# digital_clock_run4_copy.net
KiCad netlist of a schematic drawn in EasyEDA
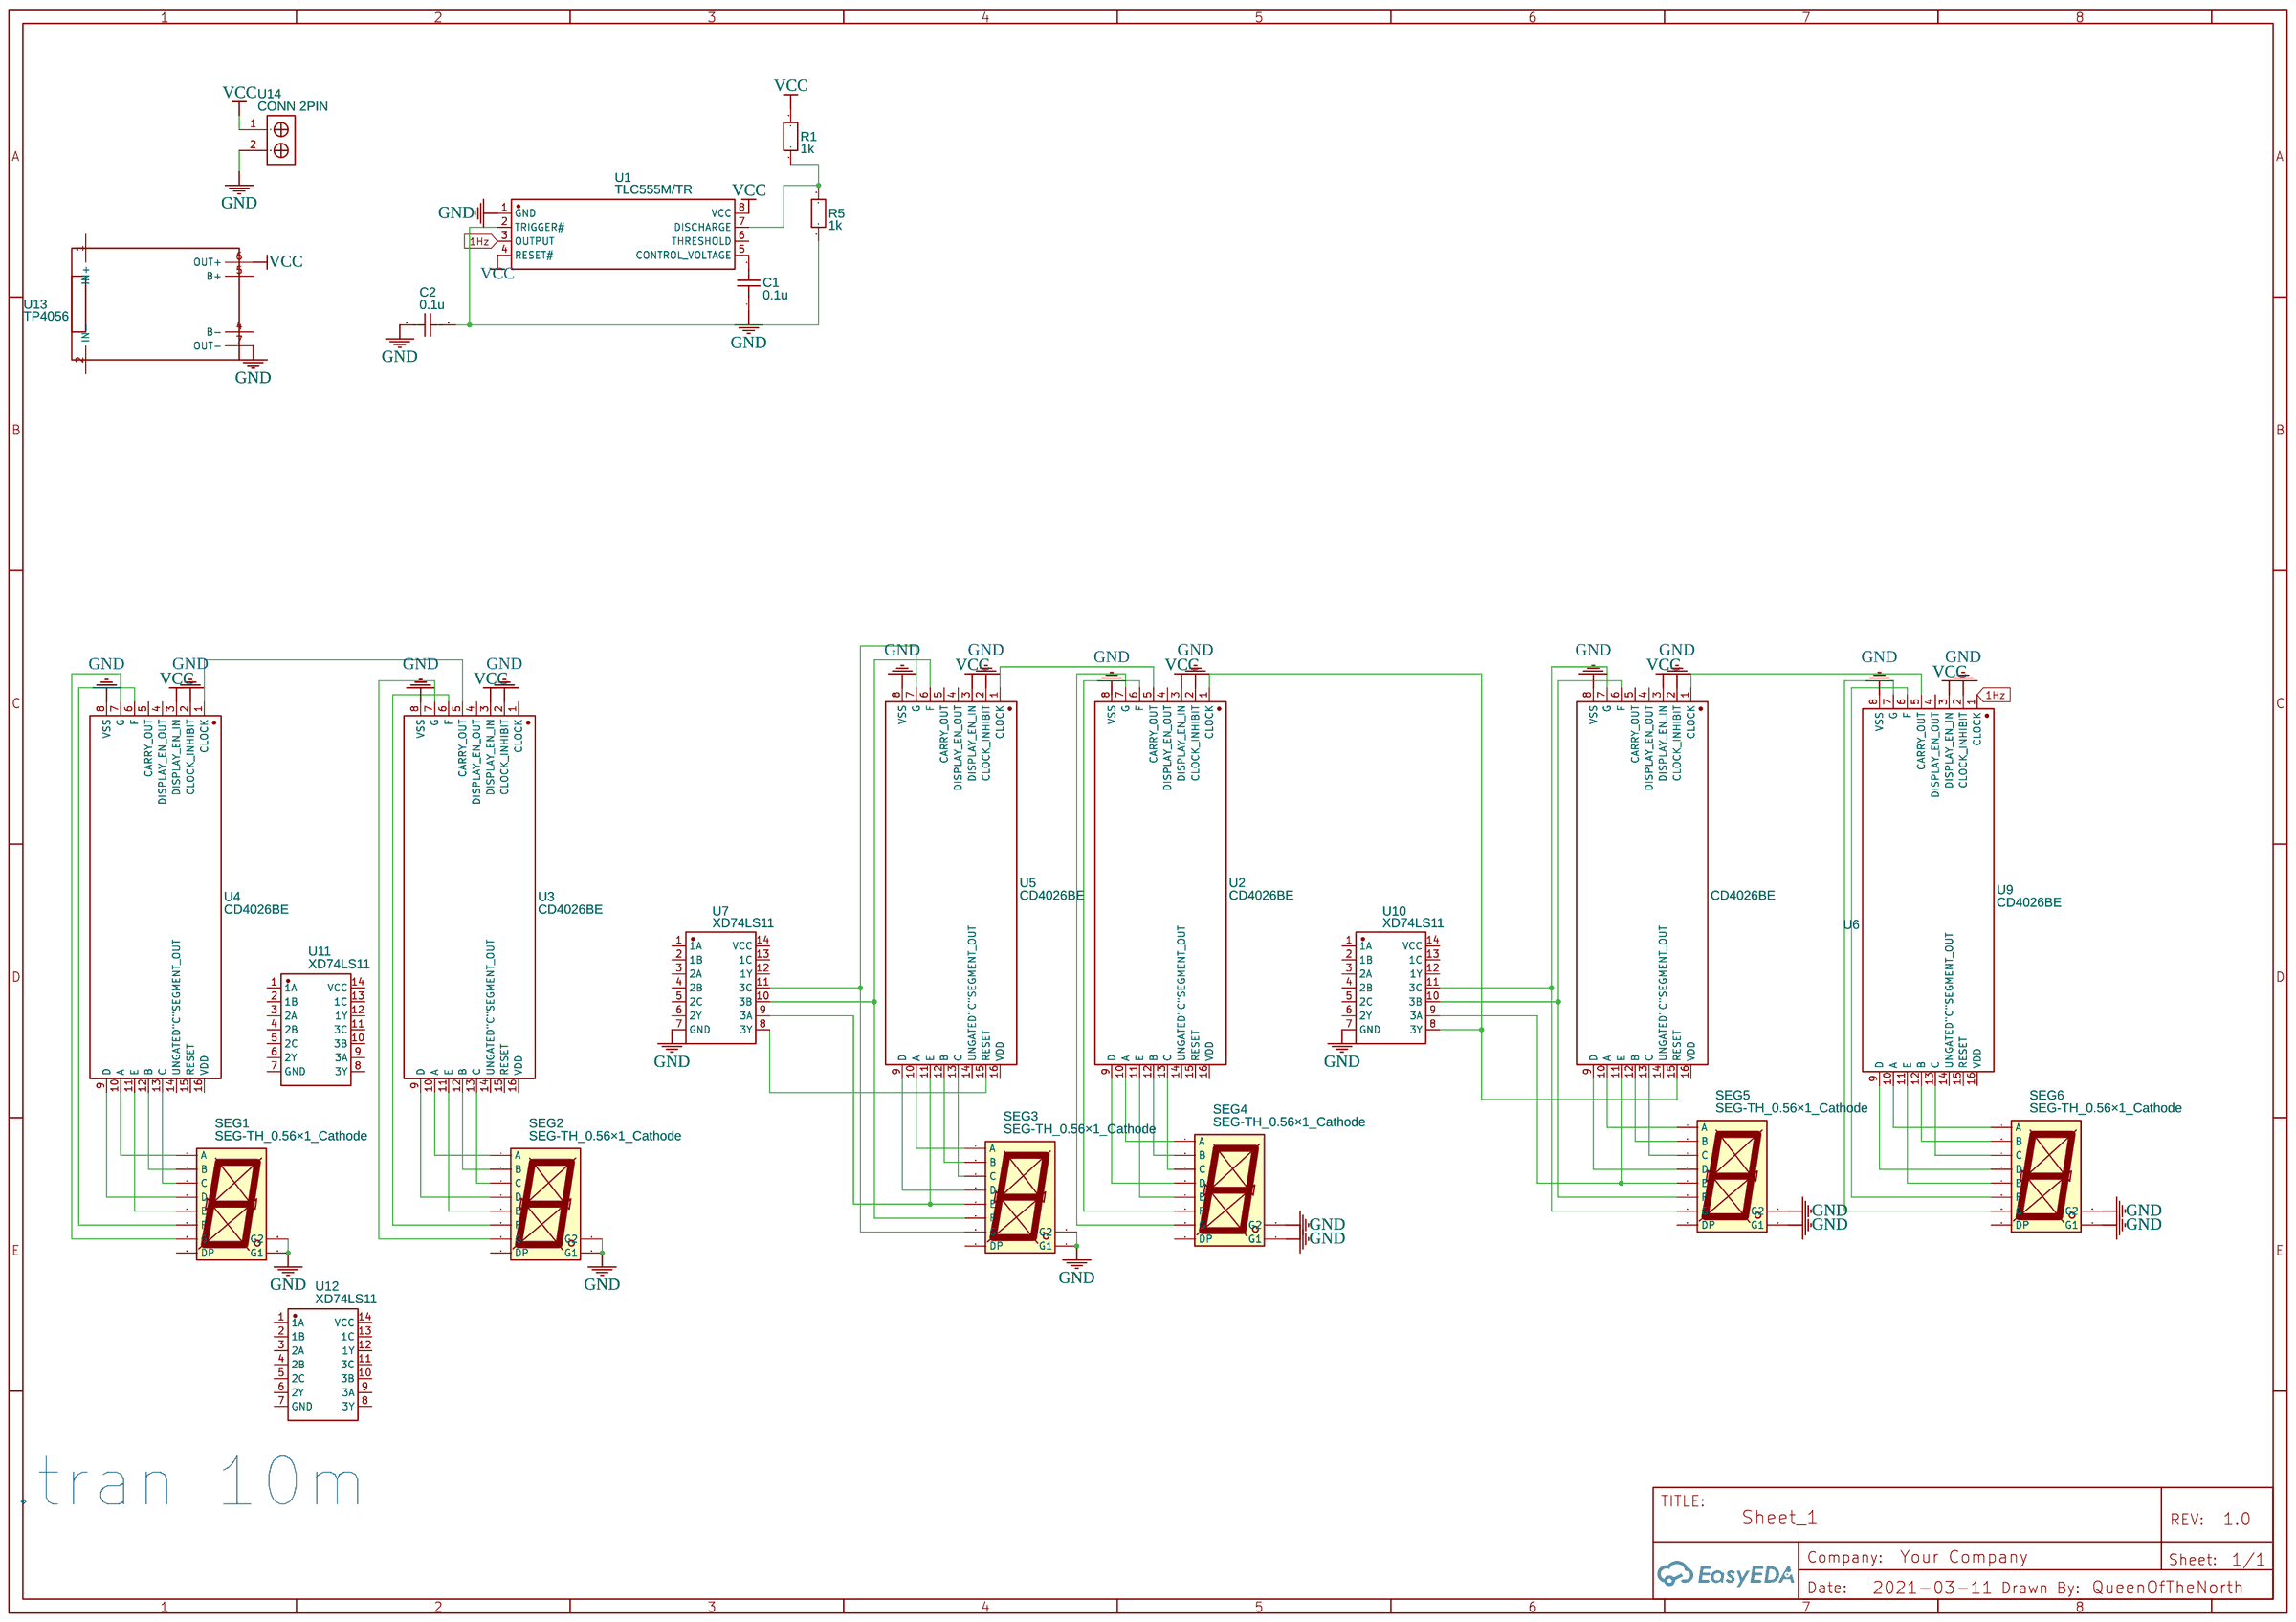
[diagram p0: schematic sheet]

(export (version "E")
  (design (tool "Eeschema 10.0.6"))
  (components
    (comp (ref "C1") (value "0.1u") (libsource (lib "") (part "C_0603_US_1")))
    (comp (ref "C2") (value "0.1u") (libsource (lib "") (part "C_0603_US")))
    (comp (ref "R1") (value "1k") (libsource (lib "") (part "R_0603_EU")))
    (comp (ref "R5") (value "1k") (libsource (lib "") (part "R_0603_EU")))
    (comp (ref "SEG1")
      (value "SEG-TH_0.56×1_Cathode")
      (fields (field (name "BOM_Supplier Part") "C8093"))
      (libsource (lib "") (part "SEG-TH_0.56×1_Cathode"))
    )
    (comp (ref "SEG2")
      (value "SEG-TH_0.56×1_Cathode")
      (fields (field (name "BOM_Supplier Part") "C8093"))
      (libsource (lib "") (part "SEG-TH_0.56×1_Cathode"))
    )
    (comp (ref "SEG3")
      (value "SEG-TH_0.56×1_Cathode")
      (fields (field (name "BOM_Supplier Part") "C8093"))
      (libsource (lib "") (part "SEG-TH_0.56×1_Cathode"))
    )
    (comp (ref "SEG4")
      (value "SEG-TH_0.56×1_Cathode")
      (fields (field (name "BOM_Supplier Part") "C8093"))
      (libsource (lib "") (part "SEG-TH_0.56×1_Cathode"))
    )
    (comp (ref "SEG5")
      (value "SEG-TH_0.56×1_Cathode")
      (fields (field (name "BOM_Supplier Part") "C8093"))
      (libsource (lib "") (part "SEG-TH_0.56×1_Cathode"))
    )
    (comp (ref "SEG6")
      (value "SEG-TH_0.56×1_Cathode")
      (fields (field (name "BOM_Supplier Part") "C8093"))
      (libsource (lib "") (part "SEG-TH_0.56×1_Cathode"))
    )
    (comp (ref "U1")
      (value "TLC555M/TR")
      (fields (field (name "BOM_Supplier Part") "C383061"))
      (libsource (lib "") (part "TLC555M/TR"))
    )
    (comp (ref "U2")
      (value "CD4026BE")
      (fields (field (name "BOM_Supplier Part") "C89909"))
      (libsource (lib "") (part "CD4026BE"))
    )
    (comp (ref "U3")
      (value "CD4026BE")
      (fields (field (name "BOM_Supplier Part") "C89909"))
      (libsource (lib "") (part "CD4026BE"))
    )
    (comp (ref "U4")
      (value "CD4026BE")
      (fields (field (name "BOM_Supplier Part") "C89909"))
      (libsource (lib "") (part "CD4026BE"))
    )
    (comp (ref "U5")
      (value "CD4026BE")
      (fields (field (name "BOM_Supplier Part") "C89909"))
      (libsource (lib "") (part "CD4026BE"))
    )
    (comp (ref "U6")
      (value "CD4026BE")
      (fields (field (name "BOM_Supplier Part") "C89909"))
      (libsource (lib "") (part "CD4026BE"))
    )
    (comp (ref "U7")
      (value "XD74LS11")
      (fields (field (name "BOM_Supplier Part") "C521167"))
      (libsource (lib "") (part "XD74LS11"))
    )
    (comp (ref "U9")
      (value "CD4026BE")
      (fields (field (name "BOM_Supplier Part") "C89909"))
      (libsource (lib "") (part "CD4026BE"))
    )
    (comp (ref "U10")
      (value "XD74LS11")
      (fields (field (name "BOM_Supplier Part") "C521167"))
      (libsource (lib "") (part "XD74LS11"))
    )
    (comp (ref "U11")
      (value "XD74LS11")
      (fields (field (name "BOM_Supplier Part") "C521167"))
      (libsource (lib "") (part "XD74LS11"))
    )
    (comp (ref "U12")
      (value "XD74LS11")
      (fields (field (name "BOM_Supplier Part") "C521167"))
      (libsource (lib "") (part "XD74LS11"))
    )
    (comp (ref "U13")
      (value "TP4056")
      (fields (field (name "BOM_Manufacturer Part") "TP4056-protect"))
      (libsource (lib "") (part "TP4056"))
    )
    (comp (ref "U14")
      (value "CONN 2PIN")
      (fields
        (field (name "BOM_Manufacturer Part") "Terminal Block")
        (field (name "BOM_Supplier Part") "undefined")
      )
      (libsource (lib "") (part "CONN 2PIN"))
    )
  )
  (nets
    (net (code "1") (name "1Hz") (class "Default")
      (node (ref "U1") (pin "3") (pinfunction "OUTPUT_3") (pintype "unspecified"))
      (node (ref "U9") (pin "1") (pinfunction "CLOCK_1") (pintype "unspecified"))
    )
    (net (code "2") (name "GND") (class "Default")
      (node (ref "C1") (pin "1") (pinfunction "1_1") (pintype "unspecified"))
      (node (ref "C2") (pin "1") (pinfunction "1_1") (pintype "unspecified"))
      (node (ref "SEG1") (pin "3") (pinfunction "G1_3") (pintype "unspecified"))
      (node (ref "SEG1") (pin "8") (pinfunction "G2_8") (pintype "unspecified"))
      (node (ref "SEG2") (pin "3") (pinfunction "G1_3") (pintype "unspecified"))
      (node (ref "SEG2") (pin "8") (pinfunction "G2_8") (pintype "unspecified"))
      (node (ref "SEG3") (pin "3") (pinfunction "G1_3") (pintype "unspecified"))
      (node (ref "SEG3") (pin "8") (pinfunction "G2_8") (pintype "unspecified"))
      (node (ref "SEG4") (pin "3") (pinfunction "G1_3") (pintype "unspecified"))
      (node (ref "SEG4") (pin "8") (pinfunction "G2_8") (pintype "unspecified"))
      (node (ref "SEG5") (pin "3") (pinfunction "G1_3") (pintype "unspecified"))
      (node (ref "SEG5") (pin "8") (pinfunction "G2_8") (pintype "unspecified"))
      (node (ref "SEG6") (pin "3") (pinfunction "G1_3") (pintype "unspecified"))
      (node (ref "SEG6") (pin "8") (pinfunction "G2_8") (pintype "unspecified"))
      (node (ref "U1") (pin "1") (pinfunction "GND_1") (pintype "unspecified"))
      (node (ref "U10") (pin "7") (pinfunction "GND_7") (pintype "unspecified"))
      (node (ref "U13") (pin "7") (pinfunction "OUT-_7") (pintype "unspecified"))
      (node (ref "U14") (pin "2") (pinfunction "2_2") (pintype "unspecified"))
      (node (ref "U2") (pin "2") (pinfunction "CLOCK_INHIBIT_2") (pintype "unspecified"))
      (node (ref "U3") (pin "2") (pinfunction "CLOCK_INHIBIT_2") (pintype "unspecified"))
      (node (ref "U3") (pin "8") (pinfunction "VSS_8") (pintype "unspecified"))
      (node (ref "U4") (pin "2") (pinfunction "CLOCK_INHIBIT_2") (pintype "unspecified"))
      (node (ref "U4") (pin "8") (pinfunction "VSS_8") (pintype "unspecified"))
      (node (ref "U5") (pin "2") (pinfunction "CLOCK_INHIBIT_2") (pintype "unspecified"))
      (node (ref "U5") (pin "8") (pinfunction "VSS_8") (pintype "unspecified"))
      (node (ref "U6") (pin "2") (pinfunction "CLOCK_INHIBIT_2") (pintype "unspecified"))
      (node (ref "U6") (pin "8") (pinfunction "VSS_8") (pintype "unspecified"))
      (node (ref "U7") (pin "7") (pinfunction "GND_7") (pintype "unspecified"))
      (node (ref "U9") (pin "2") (pinfunction "CLOCK_INHIBIT_2") (pintype "unspecified"))
      (node (ref "U9") (pin "8") (pinfunction "VSS_8") (pintype "unspecified"))
    )
    (net (code "3") (name "Net-(SEG1-A)") (class "Default")
      (node (ref "SEG1") (pin "7") (pinfunction "A_7") (pintype "unspecified"))
      (node (ref "U4") (pin "10") (pinfunction "A_10") (pintype "unspecified"))
    )
    (net (code "4") (name "Net-(SEG1-B)") (class "Default")
      (node (ref "SEG1") (pin "6") (pinfunction "B_6") (pintype "unspecified"))
      (node (ref "U4") (pin "12") (pinfunction "B_12") (pintype "unspecified"))
    )
    (net (code "5") (name "Net-(SEG1-C)") (class "Default")
      (node (ref "SEG1") (pin "4") (pinfunction "C_4") (pintype "unspecified"))
      (node (ref "U4") (pin "13") (pinfunction "C_13") (pintype "unspecified"))
    )
    (net (code "6") (name "Net-(SEG1-D)") (class "Default")
      (node (ref "SEG1") (pin "2") (pinfunction "D_2") (pintype "unspecified"))
      (node (ref "U4") (pin "9") (pinfunction "D_9") (pintype "unspecified"))
    )
    (net (code "7") (name "Net-(SEG1-E)") (class "Default")
      (node (ref "SEG1") (pin "1") (pinfunction "E_1") (pintype "unspecified"))
      (node (ref "U4") (pin "11") (pinfunction "E_11") (pintype "unspecified"))
    )
    (net (code "8") (name "Net-(SEG1-F)") (class "Default")
      (node (ref "SEG1") (pin "9") (pinfunction "F_9") (pintype "unspecified"))
      (node (ref "U4") (pin "6") (pinfunction "F_6") (pintype "unspecified"))
    )
    (net (code "9") (name "Net-(SEG1-G)") (class "Default")
      (node (ref "SEG1") (pin "10") (pinfunction "G_10") (pintype "unspecified"))
      (node (ref "U4") (pin "7") (pinfunction "G_7") (pintype "unspecified"))
    )
    (net (code "10") (name "Net-(SEG2-A)") (class "Default")
      (node (ref "SEG2") (pin "7") (pinfunction "A_7") (pintype "unspecified"))
      (node (ref "U3") (pin "10") (pinfunction "A_10") (pintype "unspecified"))
    )
    (net (code "11") (name "Net-(SEG2-B)") (class "Default")
      (node (ref "SEG2") (pin "6") (pinfunction "B_6") (pintype "unspecified"))
      (node (ref "U3") (pin "12") (pinfunction "B_12") (pintype "unspecified"))
    )
    (net (code "12") (name "Net-(SEG2-C)") (class "Default")
      (node (ref "SEG2") (pin "4") (pinfunction "C_4") (pintype "unspecified"))
      (node (ref "U3") (pin "13") (pinfunction "C_13") (pintype "unspecified"))
    )
    (net (code "13") (name "Net-(SEG2-D)") (class "Default")
      (node (ref "SEG2") (pin "2") (pinfunction "D_2") (pintype "unspecified"))
      (node (ref "U3") (pin "9") (pinfunction "D_9") (pintype "unspecified"))
    )
    (net (code "14") (name "Net-(SEG2-E)") (class "Default")
      (node (ref "SEG2") (pin "1") (pinfunction "E_1") (pintype "unspecified"))
      (node (ref "U3") (pin "11") (pinfunction "E_11") (pintype "unspecified"))
    )
    (net (code "15") (name "Net-(SEG2-F)") (class "Default")
      (node (ref "SEG2") (pin "9") (pinfunction "F_9") (pintype "unspecified"))
      (node (ref "U3") (pin "6") (pinfunction "F_6") (pintype "unspecified"))
    )
    (net (code "16") (name "Net-(SEG2-G)") (class "Default")
      (node (ref "SEG2") (pin "10") (pinfunction "G_10") (pintype "unspecified"))
      (node (ref "U3") (pin "7") (pinfunction "G_7") (pintype "unspecified"))
    )
    (net (code "17") (name "Net-(SEG3-A)") (class "Default")
      (node (ref "SEG3") (pin "7") (pinfunction "A_7") (pintype "unspecified"))
      (node (ref "U5") (pin "10") (pinfunction "A_10") (pintype "unspecified"))
    )
    (net (code "18") (name "Net-(SEG3-B)") (class "Default")
      (node (ref "SEG3") (pin "6") (pinfunction "B_6") (pintype "unspecified"))
      (node (ref "U5") (pin "12") (pinfunction "B_12") (pintype "unspecified"))
    )
    (net (code "19") (name "Net-(SEG3-C)") (class "Default")
      (node (ref "SEG3") (pin "4") (pinfunction "C_4") (pintype "unspecified"))
      (node (ref "U5") (pin "13") (pinfunction "C_13") (pintype "unspecified"))
    )
    (net (code "20") (name "Net-(SEG3-D)") (class "Default")
      (node (ref "SEG3") (pin "2") (pinfunction "D_2") (pintype "unspecified"))
      (node (ref "U5") (pin "9") (pinfunction "D_9") (pintype "unspecified"))
    )
    (net (code "21") (name "Net-(SEG3-E)") (class "Default")
      (node (ref "SEG3") (pin "1") (pinfunction "E_1") (pintype "unspecified"))
      (node (ref "U5") (pin "11") (pinfunction "E_11") (pintype "unspecified"))
      (node (ref "U7") (pin "9") (pinfunction "3A_9") (pintype "unspecified"))
    )
    (net (code "22") (name "Net-(SEG3-F)") (class "Default")
      (node (ref "SEG3") (pin "9") (pinfunction "F_9") (pintype "unspecified"))
      (node (ref "U5") (pin "6") (pinfunction "F_6") (pintype "unspecified"))
      (node (ref "U7") (pin "10") (pinfunction "3B_10") (pintype "unspecified"))
    )
    (net (code "23") (name "Net-(SEG3-G)") (class "Default")
      (node (ref "SEG3") (pin "10") (pinfunction "G_10") (pintype "unspecified"))
      (node (ref "U5") (pin "7") (pinfunction "G_7") (pintype "unspecified"))
      (node (ref "U7") (pin "11") (pinfunction "3C_11") (pintype "unspecified"))
    )
    (net (code "24") (name "Net-(SEG4-A)") (class "Default")
      (node (ref "SEG4") (pin "7") (pinfunction "A_7") (pintype "unspecified"))
      (node (ref "U2") (pin "10") (pinfunction "A_10") (pintype "unspecified"))
    )
    (net (code "25") (name "Net-(SEG4-B)") (class "Default")
      (node (ref "SEG4") (pin "6") (pinfunction "B_6") (pintype "unspecified"))
      (node (ref "U2") (pin "12") (pinfunction "B_12") (pintype "unspecified"))
    )
    (net (code "26") (name "Net-(SEG4-C)") (class "Default")
      (node (ref "SEG4") (pin "4") (pinfunction "C_4") (pintype "unspecified"))
      (node (ref "U2") (pin "13") (pinfunction "C_13") (pintype "unspecified"))
    )
    (net (code "27") (name "Net-(SEG4-D)") (class "Default")
      (node (ref "SEG4") (pin "2") (pinfunction "D_2") (pintype "unspecified"))
      (node (ref "U2") (pin "9") (pinfunction "D_9") (pintype "unspecified"))
    )
    (net (code "28") (name "Net-(SEG4-E)") (class "Default")
      (node (ref "SEG4") (pin "1") (pinfunction "E_1") (pintype "unspecified"))
      (node (ref "U2") (pin "11") (pinfunction "E_11") (pintype "unspecified"))
    )
    (net (code "29") (name "Net-(SEG4-F)") (class "Default")
      (node (ref "SEG4") (pin "9") (pinfunction "F_9") (pintype "unspecified"))
      (node (ref "U2") (pin "6") (pinfunction "F_6") (pintype "unspecified"))
    )
    (net (code "30") (name "Net-(SEG4-G)") (class "Default")
      (node (ref "SEG4") (pin "10") (pinfunction "G_10") (pintype "unspecified"))
      (node (ref "U2") (pin "7") (pinfunction "G_7") (pintype "unspecified"))
    )
    (net (code "31") (name "Net-(SEG5-A)") (class "Default")
      (node (ref "SEG5") (pin "7") (pinfunction "A_7") (pintype "unspecified"))
      (node (ref "U6") (pin "10") (pinfunction "A_10") (pintype "unspecified"))
    )
    (net (code "32") (name "Net-(SEG5-B)") (class "Default")
      (node (ref "SEG5") (pin "6") (pinfunction "B_6") (pintype "unspecified"))
      (node (ref "U6") (pin "12") (pinfunction "B_12") (pintype "unspecified"))
    )
    (net (code "33") (name "Net-(SEG5-C)") (class "Default")
      (node (ref "SEG5") (pin "4") (pinfunction "C_4") (pintype "unspecified"))
      (node (ref "U6") (pin "13") (pinfunction "C_13") (pintype "unspecified"))
    )
    (net (code "34") (name "Net-(SEG5-D)") (class "Default")
      (node (ref "SEG5") (pin "2") (pinfunction "D_2") (pintype "unspecified"))
      (node (ref "U6") (pin "9") (pinfunction "D_9") (pintype "unspecified"))
    )
    (net (code "35") (name "Net-(SEG5-E)") (class "Default")
      (node (ref "SEG5") (pin "1") (pinfunction "E_1") (pintype "unspecified"))
      (node (ref "U10") (pin "9") (pinfunction "3A_9") (pintype "unspecified"))
      (node (ref "U6") (pin "11") (pinfunction "E_11") (pintype "unspecified"))
    )
    (net (code "36") (name "Net-(SEG5-F)") (class "Default")
      (node (ref "SEG5") (pin "9") (pinfunction "F_9") (pintype "unspecified"))
      (node (ref "U10") (pin "10") (pinfunction "3B_10") (pintype "unspecified"))
      (node (ref "U6") (pin "6") (pinfunction "F_6") (pintype "unspecified"))
    )
    (net (code "37") (name "Net-(SEG5-G)") (class "Default")
      (node (ref "SEG5") (pin "10") (pinfunction "G_10") (pintype "unspecified"))
      (node (ref "U10") (pin "11") (pinfunction "3C_11") (pintype "unspecified"))
      (node (ref "U6") (pin "7") (pinfunction "G_7") (pintype "unspecified"))
    )
    (net (code "38") (name "Net-(SEG6-A)") (class "Default")
      (node (ref "SEG6") (pin "7") (pinfunction "A_7") (pintype "unspecified"))
      (node (ref "U9") (pin "10") (pinfunction "A_10") (pintype "unspecified"))
    )
    (net (code "39") (name "Net-(SEG6-B)") (class "Default")
      (node (ref "SEG6") (pin "6") (pinfunction "B_6") (pintype "unspecified"))
      (node (ref "U9") (pin "12") (pinfunction "B_12") (pintype "unspecified"))
    )
    (net (code "40") (name "Net-(SEG6-C)") (class "Default")
      (node (ref "SEG6") (pin "4") (pinfunction "C_4") (pintype "unspecified"))
      (node (ref "U9") (pin "13") (pinfunction "C_13") (pintype "unspecified"))
    )
    (net (code "41") (name "Net-(SEG6-D)") (class "Default")
      (node (ref "SEG6") (pin "2") (pinfunction "D_2") (pintype "unspecified"))
      (node (ref "U9") (pin "9") (pinfunction "D_9") (pintype "unspecified"))
    )
    (net (code "42") (name "Net-(SEG6-E)") (class "Default")
      (node (ref "SEG6") (pin "1") (pinfunction "E_1") (pintype "unspecified"))
      (node (ref "U9") (pin "11") (pinfunction "E_11") (pintype "unspecified"))
    )
    (net (code "43") (name "Net-(SEG6-F)") (class "Default")
      (node (ref "SEG6") (pin "9") (pinfunction "F_9") (pintype "unspecified"))
      (node (ref "U9") (pin "6") (pinfunction "F_6") (pintype "unspecified"))
    )
    (net (code "44") (name "Net-(SEG6-G)") (class "Default")
      (node (ref "SEG6") (pin "10") (pinfunction "G_10") (pintype "unspecified"))
      (node (ref "U9") (pin "7") (pinfunction "G_7") (pintype "unspecified"))
    )
    (net (code "45") (name "Net-(U1-CONTROL_VOLTAGE)") (class "Default")
      (node (ref "C1") (pin "2") (pinfunction "2_2") (pintype "unspecified"))
      (node (ref "U1") (pin "5") (pinfunction "CONTROL_VOLTAGE_5") (pintype "unspecified"))
    )
    (net (code "46") (name "Net-(U1-DISCHARGE)") (class "Default")
      (node (ref "R1") (pin "1") (pinfunction "1_1") (pintype "unspecified"))
      (node (ref "R5") (pin "2") (pinfunction "2_2") (pintype "unspecified"))
      (node (ref "U1") (pin "7") (pinfunction "DISCHARGE_7") (pintype "unspecified"))
    )
    (net (code "47") (name "Net-(U1-TRIGGER#)") (class "Default")
      (node (ref "C2") (pin "2") (pinfunction "2_2") (pintype "unspecified"))
      (node (ref "R5") (pin "1") (pinfunction "1_1") (pintype "unspecified"))
      (node (ref "U1") (pin "2") (pinfunction "TRIGGER#_2") (pintype "unspecified"))
    )
    (net (code "48") (name "Net-(U2-CARRY_OUT)") (class "Default")
      (node (ref "U2") (pin "5") (pinfunction "CARRY_OUT_5") (pintype "unspecified"))
      (node (ref "U5") (pin "1") (pinfunction "CLOCK_1") (pintype "unspecified"))
    )
    (net (code "49") (name "Net-(U3-CARRY_OUT)") (class "Default")
      (node (ref "U3") (pin "5") (pinfunction "CARRY_OUT_5") (pintype "unspecified"))
      (node (ref "U4") (pin "1") (pinfunction "CLOCK_1") (pintype "unspecified"))
    )
    (net (code "50") (name "Net-(U5-RESET)") (class "Default")
      (node (ref "U5") (pin "15") (pinfunction "RESET_15") (pintype "unspecified"))
      (node (ref "U7") (pin "8") (pinfunction "3Y_8") (pintype "unspecified"))
    )
    (net (code "51") (name "Net-(U6-CLOCK)") (class "Default")
      (node (ref "U6") (pin "1") (pinfunction "CLOCK_1") (pintype "unspecified"))
      (node (ref "U9") (pin "5") (pinfunction "CARRY_OUT_5") (pintype "unspecified"))
    )
    (net (code "52") (name "Net-(U10-3Y)") (class "Default")
      (node (ref "U10") (pin "8") (pinfunction "3Y_8") (pintype "unspecified"))
      (node (ref "U2") (pin "1") (pinfunction "CLOCK_1") (pintype "unspecified"))
      (node (ref "U6") (pin "15") (pinfunction "RESET_15") (pintype "unspecified"))
    )
    (net (code "53") (name "VCC") (class "Default")
      (node (ref "R1") (pin "2") (pinfunction "2_2") (pintype "unspecified"))
      (node (ref "U1") (pin "4") (pinfunction "RESET#_4") (pintype "unspecified"))
      (node (ref "U1") (pin "8") (pinfunction "VCC_8") (pintype "unspecified"))
      (node (ref "U13") (pin "6") (pinfunction "OUT+_6") (pintype "unspecified"))
      (node (ref "U14") (pin "1") (pinfunction "1_1") (pintype "unspecified"))
      (node (ref "U2") (pin "3") (pinfunction "DISPLAY_EN_IN_3") (pintype "unspecified"))
      (node (ref "U3") (pin "3") (pinfunction "DISPLAY_EN_IN_3") (pintype "unspecified"))
      (node (ref "U4") (pin "3") (pinfunction "DISPLAY_EN_IN_3") (pintype "unspecified"))
      (node (ref "U5") (pin "3") (pinfunction "DISPLAY_EN_IN_3") (pintype "unspecified"))
      (node (ref "U6") (pin "3") (pinfunction "DISPLAY_EN_IN_3") (pintype "unspecified"))
      (node (ref "U9") (pin "3") (pinfunction "DISPLAY_EN_IN_3") (pintype "unspecified"))
    )
    (net (code "54") (name "unconnected-(SEG1-DP-Pad5)") (class "Default")
      (node (ref "SEG1") (pin "5") (pinfunction "DP_5") (pintype "unspecified"))
    )
    (net (code "55") (name "unconnected-(SEG2-DP-Pad5)") (class "Default")
      (node (ref "SEG2") (pin "5") (pinfunction "DP_5") (pintype "unspecified"))
    )
    (net (code "56") (name "unconnected-(SEG3-DP-Pad5)") (class "Default")
      (node (ref "SEG3") (pin "5") (pinfunction "DP_5") (pintype "unspecified"))
    )
    (net (code "57") (name "unconnected-(SEG4-DP-Pad5)") (class "Default")
      (node (ref "SEG4") (pin "5") (pinfunction "DP_5") (pintype "unspecified"))
    )
    (net (code "58") (name "unconnected-(SEG5-DP-Pad5)") (class "Default")
      (node (ref "SEG5") (pin "5") (pinfunction "DP_5") (pintype "unspecified"))
    )
    (net (code "59") (name "unconnected-(SEG6-DP-Pad5)") (class "Default")
      (node (ref "SEG6") (pin "5") (pinfunction "DP_5") (pintype "unspecified"))
    )
    (net (code "60") (name "unconnected-(U1-THRESHOLD-Pad6)") (class "Default")
      (node (ref "U1") (pin "6") (pinfunction "THRESHOLD_6") (pintype "unspecified"))
    )
    (net (code "61") (name "unconnected-(U2-DISPLAY_EN_OUT-Pad4)") (class "Default")
      (node (ref "U2") (pin "4") (pinfunction "DISPLAY_EN_OUT_4") (pintype "unspecified"))
    )
    (net (code "62") (name "unconnected-(U2-RESET-Pad15)") (class "Default")
      (node (ref "U2") (pin "15") (pinfunction "RESET_15") (pintype "unspecified"))
    )
    (net (code "63") (name "unconnected-(U2-UNGATED\"C\"SEGMENT_OUT-Pad14)") (class "Default")
      (node (ref "U2") (pin "14") (pinfunction "UNGATED\"C\"SEGMENT_OUT_14") (pintype "unspecified"))
    )
    (net (code "64") (name "unconnected-(U2-VDD-Pad16)") (class "Default")
      (node (ref "U2") (pin "16") (pinfunction "VDD_16") (pintype "unspecified"))
    )
    (net (code "65") (name "unconnected-(U2-VSS-Pad8)") (class "Default")
      (node (ref "U2") (pin "8") (pinfunction "VSS_8") (pintype "unspecified"))
    )
    (net (code "66") (name "unconnected-(U3-CLOCK-Pad1)") (class "Default")
      (node (ref "U3") (pin "1") (pinfunction "CLOCK_1") (pintype "unspecified"))
    )
    (net (code "67") (name "unconnected-(U3-DISPLAY_EN_OUT-Pad4)") (class "Default")
      (node (ref "U3") (pin "4") (pinfunction "DISPLAY_EN_OUT_4") (pintype "unspecified"))
    )
    (net (code "68") (name "unconnected-(U3-RESET-Pad15)") (class "Default")
      (node (ref "U3") (pin "15") (pinfunction "RESET_15") (pintype "unspecified"))
    )
    (net (code "69") (name "unconnected-(U3-UNGATED\"C\"SEGMENT_OUT-Pad14)") (class "Default")
      (node (ref "U3") (pin "14") (pinfunction "UNGATED\"C\"SEGMENT_OUT_14") (pintype "unspecified"))
    )
    (net (code "70") (name "unconnected-(U3-VDD-Pad16)") (class "Default")
      (node (ref "U3") (pin "16") (pinfunction "VDD_16") (pintype "unspecified"))
    )
    (net (code "71") (name "unconnected-(U4-CARRY_OUT-Pad5)") (class "Default")
      (node (ref "U4") (pin "5") (pinfunction "CARRY_OUT_5") (pintype "unspecified"))
    )
    (net (code "72") (name "unconnected-(U4-DISPLAY_EN_OUT-Pad4)") (class "Default")
      (node (ref "U4") (pin "4") (pinfunction "DISPLAY_EN_OUT_4") (pintype "unspecified"))
    )
    (net (code "73") (name "unconnected-(U4-RESET-Pad15)") (class "Default")
      (node (ref "U4") (pin "15") (pinfunction "RESET_15") (pintype "unspecified"))
    )
    (net (code "74") (name "unconnected-(U4-UNGATED\"C\"SEGMENT_OUT-Pad14)") (class "Default")
      (node (ref "U4") (pin "14") (pinfunction "UNGATED\"C\"SEGMENT_OUT_14") (pintype "unspecified"))
    )
    (net (code "75") (name "unconnected-(U4-VDD-Pad16)") (class "Default")
      (node (ref "U4") (pin "16") (pinfunction "VDD_16") (pintype "unspecified"))
    )
    (net (code "76") (name "unconnected-(U5-CARRY_OUT-Pad5)") (class "Default")
      (node (ref "U5") (pin "5") (pinfunction "CARRY_OUT_5") (pintype "unspecified"))
    )
    (net (code "77") (name "unconnected-(U5-DISPLAY_EN_OUT-Pad4)") (class "Default")
      (node (ref "U5") (pin "4") (pinfunction "DISPLAY_EN_OUT_4") (pintype "unspecified"))
    )
    (net (code "78") (name "unconnected-(U5-UNGATED\"C\"SEGMENT_OUT-Pad14)") (class "Default")
      (node (ref "U5") (pin "14") (pinfunction "UNGATED\"C\"SEGMENT_OUT_14") (pintype "unspecified"))
    )
    (net (code "79") (name "unconnected-(U5-VDD-Pad16)") (class "Default")
      (node (ref "U5") (pin "16") (pinfunction "VDD_16") (pintype "unspecified"))
    )
    (net (code "80") (name "unconnected-(U6-CARRY_OUT-Pad5)") (class "Default")
      (node (ref "U6") (pin "5") (pinfunction "CARRY_OUT_5") (pintype "unspecified"))
    )
    (net (code "81") (name "unconnected-(U6-DISPLAY_EN_OUT-Pad4)") (class "Default")
      (node (ref "U6") (pin "4") (pinfunction "DISPLAY_EN_OUT_4") (pintype "unspecified"))
    )
    (net (code "82") (name "unconnected-(U6-UNGATED\"C\"SEGMENT_OUT-Pad14)") (class "Default")
      (node (ref "U6") (pin "14") (pinfunction "UNGATED\"C\"SEGMENT_OUT_14") (pintype "unspecified"))
    )
    (net (code "83") (name "unconnected-(U6-VDD-Pad16)") (class "Default")
      (node (ref "U6") (pin "16") (pinfunction "VDD_16") (pintype "unspecified"))
    )
    (net (code "84") (name "unconnected-(U7-1A-Pad1)") (class "Default")
      (node (ref "U7") (pin "1") (pinfunction "1A_1") (pintype "unspecified"))
    )
    (net (code "85") (name "unconnected-(U7-1B-Pad2)") (class "Default")
      (node (ref "U7") (pin "2") (pinfunction "1B_2") (pintype "unspecified"))
    )
    (net (code "86") (name "unconnected-(U7-1C-Pad13)") (class "Default")
      (node (ref "U7") (pin "13") (pinfunction "1C_13") (pintype "unspecified"))
    )
    (net (code "87") (name "unconnected-(U7-1Y-Pad12)") (class "Default")
      (node (ref "U7") (pin "12") (pinfunction "1Y_12") (pintype "unspecified"))
    )
    (net (code "88") (name "unconnected-(U7-2A-Pad3)") (class "Default")
      (node (ref "U7") (pin "3") (pinfunction "2A_3") (pintype "unspecified"))
    )
    (net (code "89") (name "unconnected-(U7-2B-Pad4)") (class "Default")
      (node (ref "U7") (pin "4") (pinfunction "2B_4") (pintype "unspecified"))
    )
    (net (code "90") (name "unconnected-(U7-2C-Pad5)") (class "Default")
      (node (ref "U7") (pin "5") (pinfunction "2C_5") (pintype "unspecified"))
    )
    (net (code "91") (name "unconnected-(U7-2Y-Pad6)") (class "Default")
      (node (ref "U7") (pin "6") (pinfunction "2Y_6") (pintype "unspecified"))
    )
    (net (code "92") (name "unconnected-(U7-VCC-Pad14)") (class "Default")
      (node (ref "U7") (pin "14") (pinfunction "VCC_14") (pintype "unspecified"))
    )
    (net (code "93") (name "unconnected-(U9-DISPLAY_EN_OUT-Pad4)") (class "Default")
      (node (ref "U9") (pin "4") (pinfunction "DISPLAY_EN_OUT_4") (pintype "unspecified"))
    )
    (net (code "94") (name "unconnected-(U9-RESET-Pad15)") (class "Default")
      (node (ref "U9") (pin "15") (pinfunction "RESET_15") (pintype "unspecified"))
    )
    (net (code "95") (name "unconnected-(U9-UNGATED\"C\"SEGMENT_OUT-Pad14)") (class "Default")
      (node (ref "U9") (pin "14") (pinfunction "UNGATED\"C\"SEGMENT_OUT_14") (pintype "unspecified"))
    )
    (net (code "96") (name "unconnected-(U9-VDD-Pad16)") (class "Default")
      (node (ref "U9") (pin "16") (pinfunction "VDD_16") (pintype "unspecified"))
    )
    (net (code "97") (name "unconnected-(U10-1A-Pad1)") (class "Default")
      (node (ref "U10") (pin "1") (pinfunction "1A_1") (pintype "unspecified"))
    )
    (net (code "98") (name "unconnected-(U10-1B-Pad2)") (class "Default")
      (node (ref "U10") (pin "2") (pinfunction "1B_2") (pintype "unspecified"))
    )
    (net (code "99") (name "unconnected-(U10-1C-Pad13)") (class "Default")
      (node (ref "U10") (pin "13") (pinfunction "1C_13") (pintype "unspecified"))
    )
    (net (code "100") (name "unconnected-(U10-1Y-Pad12)") (class "Default")
      (node (ref "U10") (pin "12") (pinfunction "1Y_12") (pintype "unspecified"))
    )
    (net (code "101") (name "unconnected-(U10-2A-Pad3)") (class "Default")
      (node (ref "U10") (pin "3") (pinfunction "2A_3") (pintype "unspecified"))
    )
    (net (code "102") (name "unconnected-(U10-2B-Pad4)") (class "Default")
      (node (ref "U10") (pin "4") (pinfunction "2B_4") (pintype "unspecified"))
    )
    (net (code "103") (name "unconnected-(U10-2C-Pad5)") (class "Default")
      (node (ref "U10") (pin "5") (pinfunction "2C_5") (pintype "unspecified"))
    )
    (net (code "104") (name "unconnected-(U10-2Y-Pad6)") (class "Default")
      (node (ref "U10") (pin "6") (pinfunction "2Y_6") (pintype "unspecified"))
    )
    (net (code "105") (name "unconnected-(U10-VCC-Pad14)") (class "Default")
      (node (ref "U10") (pin "14") (pinfunction "VCC_14") (pintype "unspecified"))
    )
    (net (code "106") (name "unconnected-(U11-1A-Pad1)") (class "Default")
      (node (ref "U11") (pin "1") (pinfunction "1A_1") (pintype "unspecified"))
    )
    (net (code "107") (name "unconnected-(U11-1B-Pad2)") (class "Default")
      (node (ref "U11") (pin "2") (pinfunction "1B_2") (pintype "unspecified"))
    )
    (net (code "108") (name "unconnected-(U11-1C-Pad13)") (class "Default")
      (node (ref "U11") (pin "13") (pinfunction "1C_13") (pintype "unspecified"))
    )
    (net (code "109") (name "unconnected-(U11-1Y-Pad12)") (class "Default")
      (node (ref "U11") (pin "12") (pinfunction "1Y_12") (pintype "unspecified"))
    )
    (net (code "110") (name "unconnected-(U11-2A-Pad3)") (class "Default")
      (node (ref "U11") (pin "3") (pinfunction "2A_3") (pintype "unspecified"))
    )
    (net (code "111") (name "unconnected-(U11-2B-Pad4)") (class "Default")
      (node (ref "U11") (pin "4") (pinfunction "2B_4") (pintype "unspecified"))
    )
    (net (code "112") (name "unconnected-(U11-2C-Pad5)") (class "Default")
      (node (ref "U11") (pin "5") (pinfunction "2C_5") (pintype "unspecified"))
    )
    (net (code "113") (name "unconnected-(U11-2Y-Pad6)") (class "Default")
      (node (ref "U11") (pin "6") (pinfunction "2Y_6") (pintype "unspecified"))
    )
    (net (code "114") (name "unconnected-(U11-3A-Pad9)") (class "Default")
      (node (ref "U11") (pin "9") (pinfunction "3A_9") (pintype "unspecified"))
    )
    (net (code "115") (name "unconnected-(U11-3B-Pad10)") (class "Default")
      (node (ref "U11") (pin "10") (pinfunction "3B_10") (pintype "unspecified"))
    )
    (net (code "116") (name "unconnected-(U11-3C-Pad11)") (class "Default")
      (node (ref "U11") (pin "11") (pinfunction "3C_11") (pintype "unspecified"))
    )
    (net (code "117") (name "unconnected-(U11-3Y-Pad8)") (class "Default")
      (node (ref "U11") (pin "8") (pinfunction "3Y_8") (pintype "unspecified"))
    )
    (net (code "118") (name "unconnected-(U11-GND-Pad7)") (class "Default")
      (node (ref "U11") (pin "7") (pinfunction "GND_7") (pintype "unspecified"))
    )
    (net (code "119") (name "unconnected-(U11-VCC-Pad14)") (class "Default")
      (node (ref "U11") (pin "14") (pinfunction "VCC_14") (pintype "unspecified"))
    )
    (net (code "120") (name "unconnected-(U12-1A-Pad1)") (class "Default")
      (node (ref "U12") (pin "1") (pinfunction "1A_1") (pintype "unspecified"))
    )
    (net (code "121") (name "unconnected-(U12-1B-Pad2)") (class "Default")
      (node (ref "U12") (pin "2") (pinfunction "1B_2") (pintype "unspecified"))
    )
    (net (code "122") (name "unconnected-(U12-1C-Pad13)") (class "Default")
      (node (ref "U12") (pin "13") (pinfunction "1C_13") (pintype "unspecified"))
    )
    (net (code "123") (name "unconnected-(U12-1Y-Pad12)") (class "Default")
      (node (ref "U12") (pin "12") (pinfunction "1Y_12") (pintype "unspecified"))
    )
    (net (code "124") (name "unconnected-(U12-2A-Pad3)") (class "Default")
      (node (ref "U12") (pin "3") (pinfunction "2A_3") (pintype "unspecified"))
    )
    (net (code "125") (name "unconnected-(U12-2B-Pad4)") (class "Default")
      (node (ref "U12") (pin "4") (pinfunction "2B_4") (pintype "unspecified"))
    )
    (net (code "126") (name "unconnected-(U12-2C-Pad5)") (class "Default")
      (node (ref "U12") (pin "5") (pinfunction "2C_5") (pintype "unspecified"))
    )
    (net (code "127") (name "unconnected-(U12-2Y-Pad6)") (class "Default")
      (node (ref "U12") (pin "6") (pinfunction "2Y_6") (pintype "unspecified"))
    )
    (net (code "128") (name "unconnected-(U12-3A-Pad9)") (class "Default")
      (node (ref "U12") (pin "9") (pinfunction "3A_9") (pintype "unspecified"))
    )
    (net (code "129") (name "unconnected-(U12-3B-Pad10)") (class "Default")
      (node (ref "U12") (pin "10") (pinfunction "3B_10") (pintype "unspecified"))
    )
    (net (code "130") (name "unconnected-(U12-3C-Pad11)") (class "Default")
      (node (ref "U12") (pin "11") (pinfunction "3C_11") (pintype "unspecified"))
    )
    (net (code "131") (name "unconnected-(U12-3Y-Pad8)") (class "Default")
      (node (ref "U12") (pin "8") (pinfunction "3Y_8") (pintype "unspecified"))
    )
    (net (code "132") (name "unconnected-(U12-GND-Pad7)") (class "Default")
      (node (ref "U12") (pin "7") (pinfunction "GND_7") (pintype "unspecified"))
    )
    (net (code "133") (name "unconnected-(U12-VCC-Pad14)") (class "Default")
      (node (ref "U12") (pin "14") (pinfunction "VCC_14") (pintype "unspecified"))
    )
    (net (code "134") (name "unconnected-(U13-B+-Pad5)") (class "Default")
      (node (ref "U13") (pin "5") (pinfunction "B+_5") (pintype "unspecified"))
    )
    (net (code "135") (name "unconnected-(U13-B--Pad4)") (class "Default")
      (node (ref "U13") (pin "4") (pinfunction "B-_4") (pintype "unspecified"))
    )
    (net (code "136") (name "unconnected-(U13-IN+-Pad1)") (class "Default")
      (node (ref "U13") (pin "1") (pinfunction "IN+_1") (pintype "unspecified"))
    )
    (net (code "137") (name "unconnected-(U13-IN--Pad2)") (class "Default")
      (node (ref "U13") (pin "2") (pinfunction "IN-_2") (pintype "unspecified"))
    )
  )
)
